# Sheet1.net
KiCad netlist of a schematic drawn in Altium Designer
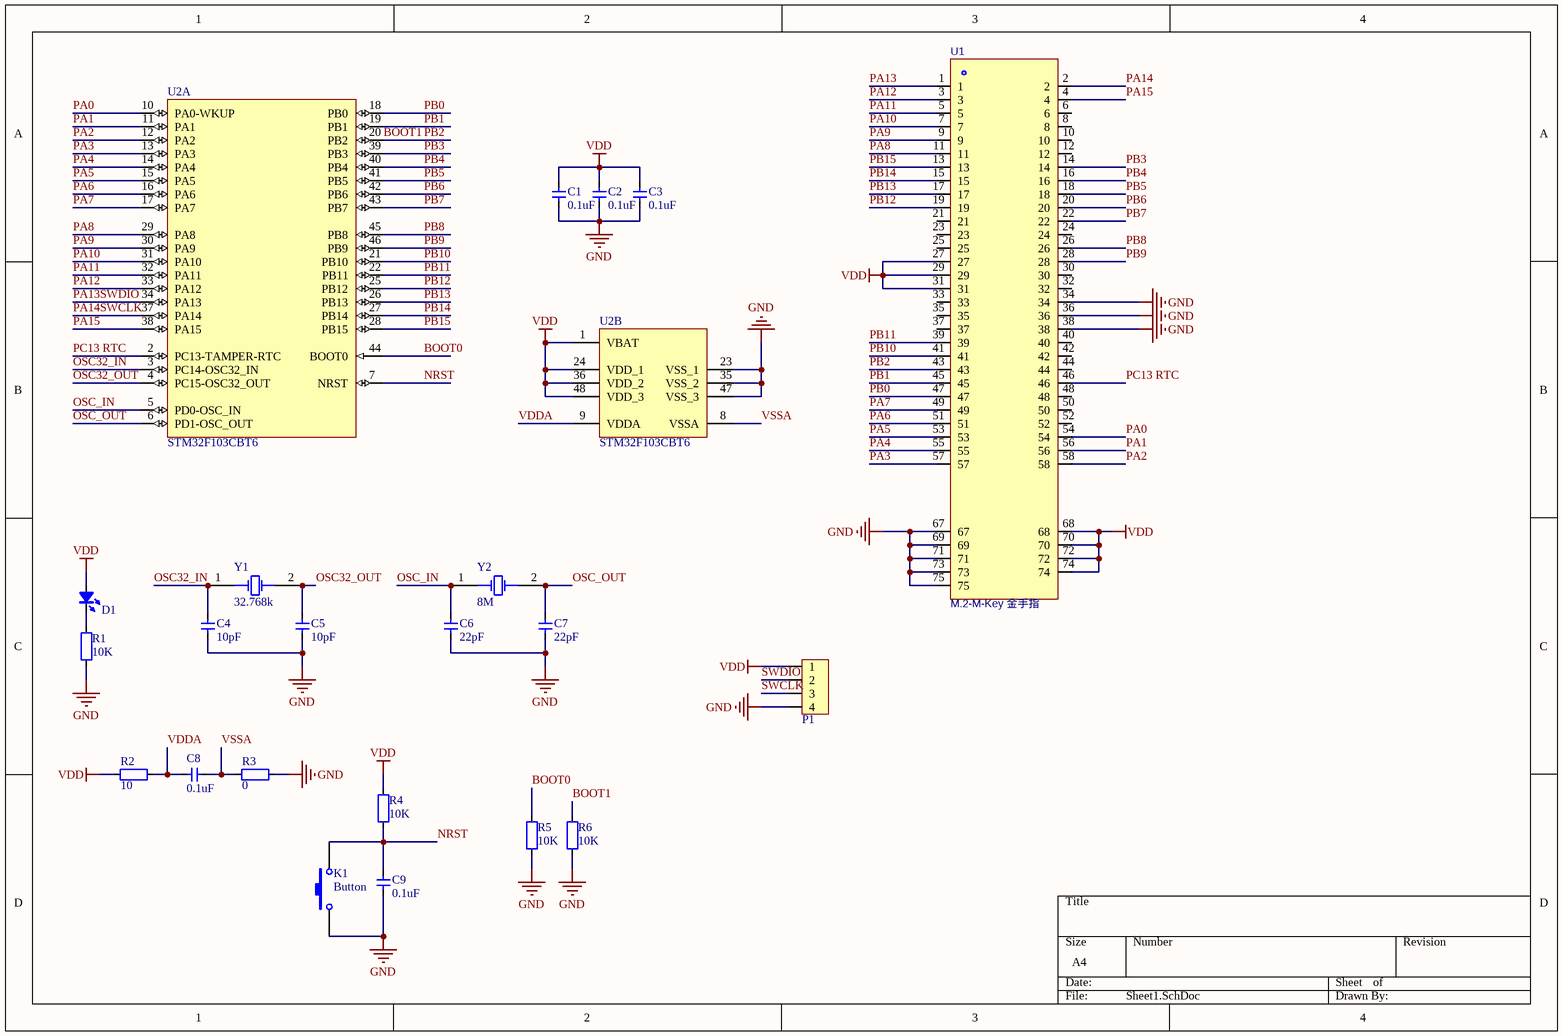
[diagram p0: Sheet1.SchDoc]

(export (version "E")
  (design (tool "Eeschema 10.0.6"))
  (components
    (comp (ref "C1")
      (value "0.1uF")
      (footprint "C0603")
      (description "Capacitor")
      (fields (field (name "PUBLISHER") "Altium Limited"))
      (libsource (lib "lycraft_lib") (part "贴片C"))
    )
    (comp (ref "C2")
      (value "0.1uF")
      (footprint "C0603")
      (description "Capacitor")
      (fields (field (name "PUBLISHER") "Altium Limited"))
      (libsource (lib "lycraft_lib") (part "贴片C"))
    )
    (comp (ref "C3")
      (value "0.1uF")
      (footprint "C0603")
      (description "Capacitor")
      (fields (field (name "PUBLISHER") "Altium Limited"))
      (libsource (lib "lycraft_lib") (part "贴片C"))
    )
    (comp (ref "C4")
      (value "10pF")
      (footprint "C0603")
      (description "Capacitor")
      (fields (field (name "PUBLISHER") "Altium Limited"))
      (libsource (lib "lycraft_lib") (part "贴片C"))
    )
    (comp (ref "C5")
      (value "10pF")
      (footprint "C0603")
      (description "Capacitor")
      (fields (field (name "PUBLISHER") "Altium Limited"))
      (libsource (lib "lycraft_lib") (part "贴片C"))
    )
    (comp (ref "C6")
      (value "22pF")
      (footprint "C0603")
      (description "Capacitor")
      (fields (field (name "PUBLISHER") "Altium Limited"))
      (libsource (lib "lycraft_lib") (part "贴片C"))
    )
    (comp (ref "C7")
      (value "22pF")
      (footprint "C0603")
      (description "Capacitor")
      (fields (field (name "PUBLISHER") "Altium Limited"))
      (libsource (lib "lycraft_lib") (part "贴片C"))
    )
    (comp (ref "C8")
      (value "0.1uF")
      (footprint "C0603")
      (description "Capacitor")
      (fields (field (name "PUBLISHER") "Altium Limited"))
      (libsource (lib "lycraft_lib") (part "贴片C"))
    )
    (comp (ref "C9")
      (value "0.1uF")
      (footprint "C0603")
      (description "Capacitor")
      (fields (field (name "PUBLISHER") "Altium Limited"))
      (libsource (lib "lycraft_lib") (part "贴片C"))
    )
    (comp (ref "D1")
      (value "color?")
      (footprint "LED0603")
      (description "LED")
      (libsource (lib "lycraft_lib") (part "贴片LED"))
    )
    (comp (ref "K1")
      (value "Button")
      (footprint "BUTTON-K2")
      (fields (field (name "PUBLISHER") "Altium Limited"))
      (libsource (lib "lycraft_lib") (part "Button"))
    )
    (comp (ref "P1")
      (value "HDR1x4_2.0")
      (footprint "HDR 4_2")
      (libsource (lib "Pzh_Lib") (part "HDR1x4_2.0"))
    )
    (comp (ref "R1")
      (value "10K")
      (footprint "R0603")
      (description "Resistor")
      (fields (field (name "PUBLISHER") "Altium Limited"))
      (libsource (lib "lycraft_lib") (part "贴片R"))
    )
    (comp (ref "R2")
      (value "10")
      (footprint "R0603")
      (description "Resistor")
      (fields (field (name "PUBLISHER") "Altium Limited"))
      (libsource (lib "") (part "贴片R_1"))
    )
    (comp (ref "R3")
      (value "0")
      (footprint "R0603")
      (description "Resistor")
      (fields (field (name "PUBLISHER") "Altium Limited"))
      (libsource (lib "") (part "贴片R_1"))
    )
    (comp (ref "R4")
      (value "10K")
      (footprint "R0603")
      (description "Resistor")
      (fields (field (name "PUBLISHER") "Altium Limited"))
      (libsource (lib "lycraft_lib") (part "贴片R"))
    )
    (comp (ref "R5")
      (value "10K")
      (footprint "R0603")
      (description "Resistor")
      (fields (field (name "PUBLISHER") "Altium Limited"))
      (libsource (lib "lycraft_lib") (part "贴片R"))
    )
    (comp (ref "R6")
      (value "10K")
      (footprint "R0603")
      (description "Resistor")
      (fields (field (name "PUBLISHER") "Altium Limited"))
      (libsource (lib "lycraft_lib") (part "贴片R"))
    )
    (comp (ref "U1")
      (value "M.2-M-Key 金手指")
      (footprint "M.2_NGFF")
      (fields (field (name "CONTRIBUTOR") "zengjf"))
      (libsource (lib "接插件") (part "M.2-M-Key 金手指"))
    )
    (comp (ref "U2")
      (value "STM32F103CBT6")
      (footprint "STM-LQFP48_N")
      (libsource (lib "MCU") (part "STM32F103CBT6"))
    )
    (comp (ref "Y1")
      (value "XTAL 32.768KHz 2P")
      (footprint "3215 2Pin")
      (fields (field (name "ALTIUM_UNNAMED_1") "32.768k"))
      (libsource (lib "lycraft_lib") (part "XTAL 32.768KHz 2P"))
    )
    (comp (ref "Y2")
      (value "8M")
      (footprint "5032 2Pin")
      (libsource (lib "lycraft_lib") (part "XTAL 8Mhz 2pin"))
    )
  )
  (nets
    (net (code "1") (name "/BOOT0") (class "Default")
      (node (ref "R5") (pin "2") (pinfunction "2_2") (pintype "passive"))
      (node (ref "U2") (pin "44") (pinfunction "BOOT0_44") (pintype "input"))
    )
    (net (code "2") (name "/BOOT1") (class "Default")
      (node (ref "R6") (pin "2") (pinfunction "2_2") (pintype "passive"))
      (node (ref "U1") (pin "43") (pinfunction "43_43") (pintype "passive"))
      (node (ref "U2") (pin "20") (pinfunction "PB2_20") (pintype "bidirectional"))
    )
    (net (code "3") (name "/NRST") (class "Default")
      (node (ref "C9") (pin "2") (pinfunction "2_2") (pintype "passive"))
      (node (ref "K1") (pin "2") (pinfunction "2_2") (pintype "passive"))
      (node (ref "R4") (pin "1") (pinfunction "1_1") (pintype "passive"))
      (node (ref "U2") (pin "7") (pinfunction "NRST_7") (pintype "bidirectional"))
    )
    (net (code "4") (name "/OSC32_IN") (class "Default")
      (node (ref "C4") (pin "2") (pinfunction "2_2") (pintype "passive"))
      (node (ref "U2") (pin "3") (pinfunction "PC14-OSC32_IN_3") (pintype "bidirectional"))
      (node (ref "Y1") (pin "1") (pinfunction "OSC1_1") (pintype "passive"))
    )
    (net (code "5") (name "/OSC32_OUT") (class "Default")
      (node (ref "C5") (pin "2") (pinfunction "2_2") (pintype "passive"))
      (node (ref "U2") (pin "4") (pinfunction "PC15-OSC32_OUT_4") (pintype "bidirectional"))
      (node (ref "Y1") (pin "2") (pinfunction "OSC2_2") (pintype "passive"))
    )
    (net (code "6") (name "/OSC_IN") (class "Default")
      (node (ref "C6") (pin "2") (pinfunction "2_2") (pintype "passive"))
      (node (ref "U2") (pin "5") (pinfunction "PD0-OSC_IN_5") (pintype "bidirectional"))
      (node (ref "Y2") (pin "1") (pinfunction "OSC1_1") (pintype "passive"))
    )
    (net (code "7") (name "/OSC_OUT") (class "Default")
      (node (ref "C7") (pin "2") (pinfunction "2_2") (pintype "passive"))
      (node (ref "U2") (pin "6") (pinfunction "PD1-OSC_OUT_6") (pintype "bidirectional"))
      (node (ref "Y2") (pin "2") (pinfunction "OSC2_2") (pintype "passive"))
    )
    (net (code "8") (name "/PA0") (class "Default")
      (node (ref "U1") (pin "54") (pinfunction "54_54") (pintype "passive"))
      (node (ref "U2") (pin "10") (pinfunction "PA0-WKUP_10") (pintype "bidirectional"))
    )
    (net (code "9") (name "/PA1") (class "Default")
      (node (ref "U1") (pin "56") (pinfunction "56_56") (pintype "passive"))
      (node (ref "U2") (pin "11") (pinfunction "PA1_11") (pintype "bidirectional"))
    )
    (net (code "10") (name "/PA2") (class "Default")
      (node (ref "U1") (pin "58") (pinfunction "58_58") (pintype "passive"))
      (node (ref "U2") (pin "12") (pinfunction "PA2_12") (pintype "bidirectional"))
    )
    (net (code "11") (name "/PA3") (class "Default")
      (node (ref "U1") (pin "57") (pinfunction "57_57") (pintype "passive"))
      (node (ref "U2") (pin "13") (pinfunction "PA3_13") (pintype "bidirectional"))
    )
    (net (code "12") (name "/PA4") (class "Default")
      (node (ref "U1") (pin "55") (pinfunction "55_55") (pintype "passive"))
      (node (ref "U2") (pin "14") (pinfunction "PA4_14") (pintype "bidirectional"))
    )
    (net (code "13") (name "/PA5") (class "Default")
      (node (ref "U1") (pin "53") (pinfunction "53_53") (pintype "passive"))
      (node (ref "U2") (pin "15") (pinfunction "PA5_15") (pintype "bidirectional"))
    )
    (net (code "14") (name "/PA6") (class "Default")
      (node (ref "U1") (pin "51") (pinfunction "51_51") (pintype "passive"))
      (node (ref "U2") (pin "16") (pinfunction "PA6_16") (pintype "bidirectional"))
    )
    (net (code "15") (name "/PA7") (class "Default")
      (node (ref "U1") (pin "49") (pinfunction "49_49") (pintype "passive"))
      (node (ref "U2") (pin "17") (pinfunction "PA7_17") (pintype "bidirectional"))
    )
    (net (code "16") (name "/PA8") (class "Default")
      (node (ref "U1") (pin "11") (pinfunction "11_11") (pintype "passive"))
      (node (ref "U2") (pin "29") (pinfunction "PA8_29") (pintype "bidirectional"))
    )
    (net (code "17") (name "/PA9") (class "Default")
      (node (ref "U1") (pin "9") (pinfunction "9_9") (pintype "passive"))
      (node (ref "U2") (pin "30") (pinfunction "PA9_30") (pintype "bidirectional"))
    )
    (net (code "18") (name "/PA10") (class "Default")
      (node (ref "U1") (pin "7") (pinfunction "7_7") (pintype "passive"))
      (node (ref "U2") (pin "31") (pinfunction "PA10_31") (pintype "bidirectional"))
    )
    (net (code "19") (name "/PA11") (class "Default")
      (node (ref "U1") (pin "5") (pinfunction "5_5") (pintype "passive"))
      (node (ref "U2") (pin "32") (pinfunction "PA11_32") (pintype "bidirectional"))
    )
    (net (code "20") (name "/PA12") (class "Default")
      (node (ref "U1") (pin "3") (pinfunction "3_3") (pintype "passive"))
      (node (ref "U2") (pin "33") (pinfunction "PA12_33") (pintype "bidirectional"))
    )
    (net (code "21") (name "/PA13") (class "Default")
      (node (ref "P1") (pin "2") (pinfunction "2_2") (pintype "passive"))
      (node (ref "U1") (pin "1") (pinfunction "1_1") (pintype "passive"))
      (node (ref "U2") (pin "34") (pinfunction "PA13_34") (pintype "bidirectional"))
    )
    (net (code "22") (name "/PA14") (class "Default")
      (node (ref "P1") (pin "3") (pinfunction "3_3") (pintype "passive"))
      (node (ref "U1") (pin "2") (pinfunction "2_2") (pintype "passive"))
      (node (ref "U2") (pin "37") (pinfunction "PA14_37") (pintype "bidirectional"))
    )
    (net (code "23") (name "/PA15") (class "Default")
      (node (ref "U1") (pin "4") (pinfunction "4_4") (pintype "passive"))
      (node (ref "U2") (pin "38") (pinfunction "PA15_38") (pintype "bidirectional"))
    )
    (net (code "24") (name "/PB0") (class "Default")
      (node (ref "U1") (pin "47") (pinfunction "47_47") (pintype "passive"))
      (node (ref "U2") (pin "18") (pinfunction "PB0_18") (pintype "bidirectional"))
    )
    (net (code "25") (name "/PB1") (class "Default")
      (node (ref "U1") (pin "45") (pinfunction "45_45") (pintype "passive"))
      (node (ref "U2") (pin "19") (pinfunction "PB1_19") (pintype "bidirectional"))
    )
    (net (code "26") (name "/PB3") (class "Default")
      (node (ref "U1") (pin "14") (pinfunction "14_14") (pintype "passive"))
      (node (ref "U2") (pin "39") (pinfunction "PB3_39") (pintype "bidirectional"))
    )
    (net (code "27") (name "/PB4") (class "Default")
      (node (ref "U1") (pin "16") (pinfunction "16_16") (pintype "passive"))
      (node (ref "U2") (pin "40") (pinfunction "PB4_40") (pintype "bidirectional"))
    )
    (net (code "28") (name "/PB5") (class "Default")
      (node (ref "U1") (pin "18") (pinfunction "18_18") (pintype "passive"))
      (node (ref "U2") (pin "41") (pinfunction "PB5_41") (pintype "bidirectional"))
    )
    (net (code "29") (name "/PB6") (class "Default")
      (node (ref "U1") (pin "20") (pinfunction "20_20") (pintype "passive"))
      (node (ref "U2") (pin "42") (pinfunction "PB6_42") (pintype "bidirectional"))
    )
    (net (code "30") (name "/PB7") (class "Default")
      (node (ref "U1") (pin "22") (pinfunction "22_22") (pintype "passive"))
      (node (ref "U2") (pin "43") (pinfunction "PB7_43") (pintype "bidirectional"))
    )
    (net (code "31") (name "/PB8") (class "Default")
      (node (ref "U1") (pin "26") (pinfunction "26_26") (pintype "passive"))
      (node (ref "U2") (pin "45") (pinfunction "PB8_45") (pintype "bidirectional"))
    )
    (net (code "32") (name "/PB9") (class "Default")
      (node (ref "U1") (pin "28") (pinfunction "28_28") (pintype "passive"))
      (node (ref "U2") (pin "46") (pinfunction "PB9_46") (pintype "bidirectional"))
    )
    (net (code "33") (name "/PB10") (class "Default")
      (node (ref "U1") (pin "41") (pinfunction "41_41") (pintype "passive"))
      (node (ref "U2") (pin "21") (pinfunction "PB10_21") (pintype "bidirectional"))
    )
    (net (code "34") (name "/PB11") (class "Default")
      (node (ref "U1") (pin "39") (pinfunction "39_39") (pintype "passive"))
      (node (ref "U2") (pin "22") (pinfunction "PB11_22") (pintype "bidirectional"))
    )
    (net (code "35") (name "/PB12") (class "Default")
      (node (ref "U1") (pin "19") (pinfunction "19_19") (pintype "passive"))
      (node (ref "U2") (pin "25") (pinfunction "PB12_25") (pintype "bidirectional"))
    )
    (net (code "36") (name "/PB13") (class "Default")
      (node (ref "U1") (pin "17") (pinfunction "17_17") (pintype "passive"))
      (node (ref "U2") (pin "26") (pinfunction "PB13_26") (pintype "bidirectional"))
    )
    (net (code "37") (name "/PB14") (class "Default")
      (node (ref "U1") (pin "15") (pinfunction "15_15") (pintype "passive"))
      (node (ref "U2") (pin "27") (pinfunction "PB14_27") (pintype "bidirectional"))
    )
    (net (code "38") (name "/PB15") (class "Default")
      (node (ref "U1") (pin "13") (pinfunction "13_13") (pintype "passive"))
      (node (ref "U2") (pin "28") (pinfunction "PB15_28") (pintype "bidirectional"))
    )
    (net (code "39") (name "/PC13 RTC") (class "Default")
      (node (ref "U1") (pin "46") (pinfunction "46_46") (pintype "passive"))
      (node (ref "U2") (pin "2") (pinfunction "PC13-TAMPER-RTC_2") (pintype "bidirectional"))
    )
    (net (code "40") (name "/VDDA") (class "Default")
      (node (ref "C8") (pin "1") (pinfunction "1_1") (pintype "passive"))
      (node (ref "R2") (pin "2") (pinfunction "2_2") (pintype "passive"))
      (node (ref "U2") (pin "9") (pinfunction "VDDA_9") (pintype "power_in"))
    )
    (net (code "41") (name "/VSSA") (class "Default")
      (node (ref "C8") (pin "2") (pinfunction "2_2") (pintype "passive"))
      (node (ref "R3") (pin "1") (pinfunction "1_1") (pintype "passive"))
      (node (ref "U2") (pin "8") (pinfunction "VSSA_8") (pintype "power_in"))
    )
    (net (code "42") (name "GND") (class "Default")
      (node (ref "C1") (pin "1") (pinfunction "1_1") (pintype "passive"))
      (node (ref "C2") (pin "1") (pinfunction "1_1") (pintype "passive"))
      (node (ref "C3") (pin "1") (pinfunction "1_1") (pintype "passive"))
      (node (ref "C4") (pin "1") (pinfunction "1_1") (pintype "passive"))
      (node (ref "C5") (pin "1") (pinfunction "1_1") (pintype "passive"))
      (node (ref "C6") (pin "1") (pinfunction "1_1") (pintype "passive"))
      (node (ref "C7") (pin "1") (pinfunction "1_1") (pintype "passive"))
      (node (ref "C9") (pin "1") (pinfunction "1_1") (pintype "passive"))
      (node (ref "K1") (pin "1") (pinfunction "1_1") (pintype "passive"))
      (node (ref "P1") (pin "4") (pinfunction "4_4") (pintype "passive"))
      (node (ref "R1") (pin "1") (pinfunction "1_1") (pintype "passive"))
      (node (ref "R3") (pin "2") (pinfunction "2_2") (pintype "passive"))
      (node (ref "R5") (pin "1") (pinfunction "1_1") (pintype "passive"))
      (node (ref "R6") (pin "1") (pinfunction "1_1") (pintype "passive"))
      (node (ref "U1") (pin "34") (pinfunction "34_34") (pintype "passive"))
      (node (ref "U1") (pin "36") (pinfunction "36_36") (pintype "passive"))
      (node (ref "U1") (pin "38") (pinfunction "38_38") (pintype "passive"))
      (node (ref "U1") (pin "67") (pinfunction "67_67") (pintype "passive"))
      (node (ref "U1") (pin "69") (pinfunction "69_69") (pintype "passive"))
      (node (ref "U1") (pin "71") (pinfunction "71_71") (pintype "passive"))
      (node (ref "U1") (pin "73") (pinfunction "73_73") (pintype "passive"))
      (node (ref "U1") (pin "75") (pinfunction "75_75") (pintype "passive"))
      (node (ref "U2") (pin "23") (pinfunction "VSS_1_23") (pintype "power_in"))
      (node (ref "U2") (pin "35") (pinfunction "VSS_2_35") (pintype "power_in"))
      (node (ref "U2") (pin "47") (pinfunction "VSS_3_47") (pintype "power_in"))
    )
    (net (code "43") (name "Net-(D1-K)") (class "Default")
      (node (ref "D1") (pin "2") (pinfunction "K_2") (pintype "passive"))
      (node (ref "R1") (pin "2") (pinfunction "2_2") (pintype "passive"))
    )
    (net (code "44") (name "VDD") (class "Default")
      (node (ref "C1") (pin "2") (pinfunction "2_2") (pintype "passive"))
      (node (ref "C2") (pin "2") (pinfunction "2_2") (pintype "passive"))
      (node (ref "C3") (pin "2") (pinfunction "2_2") (pintype "passive"))
      (node (ref "D1") (pin "1") (pinfunction "A_1") (pintype "passive"))
      (node (ref "P1") (pin "1") (pinfunction "1_1") (pintype "passive"))
      (node (ref "R2") (pin "1") (pinfunction "1_1") (pintype "passive"))
      (node (ref "R4") (pin "2") (pinfunction "2_2") (pintype "passive"))
      (node (ref "U1") (pin "27") (pinfunction "27_27") (pintype "passive"))
      (node (ref "U1") (pin "29") (pinfunction "29_29") (pintype "passive"))
      (node (ref "U1") (pin "31") (pinfunction "31_31") (pintype "passive"))
      (node (ref "U1") (pin "68") (pinfunction "68_68") (pintype "passive"))
      (node (ref "U1") (pin "70") (pinfunction "70_70") (pintype "passive"))
      (node (ref "U1") (pin "72") (pinfunction "72_72") (pintype "passive"))
      (node (ref "U1") (pin "74") (pinfunction "74_74") (pintype "passive"))
      (node (ref "U2") (pin "1") (pinfunction "VBAT_1") (pintype "power_in"))
      (node (ref "U2") (pin "24") (pinfunction "VDD_1_24") (pintype "power_in"))
      (node (ref "U2") (pin "36") (pinfunction "VDD_2_36") (pintype "power_in"))
      (node (ref "U2") (pin "48") (pinfunction "VDD_3_48") (pintype "power_in"))
    )
    (net (code "45") (name "unconnected-(U1-Pad6)") (class "Default")
      (node (ref "U1") (pin "6") (pinfunction "6_6") (pintype "passive"))
    )
    (net (code "46") (name "unconnected-(U1-Pad8)") (class "Default")
      (node (ref "U1") (pin "8") (pinfunction "8_8") (pintype "passive"))
    )
    (net (code "47") (name "unconnected-(U1-Pad10)") (class "Default")
      (node (ref "U1") (pin "10") (pinfunction "10_10") (pintype "passive"))
    )
    (net (code "48") (name "unconnected-(U1-Pad12)") (class "Default")
      (node (ref "U1") (pin "12") (pinfunction "12_12") (pintype "passive"))
    )
    (net (code "49") (name "unconnected-(U1-Pad21)") (class "Default")
      (node (ref "U1") (pin "21") (pinfunction "21_21") (pintype "passive"))
    )
    (net (code "50") (name "unconnected-(U1-Pad23)") (class "Default")
      (node (ref "U1") (pin "23") (pinfunction "23_23") (pintype "passive"))
    )
    (net (code "51") (name "unconnected-(U1-Pad24)") (class "Default")
      (node (ref "U1") (pin "24") (pinfunction "24_24") (pintype "passive"))
    )
    (net (code "52") (name "unconnected-(U1-Pad25)") (class "Default")
      (node (ref "U1") (pin "25") (pinfunction "25_25") (pintype "passive"))
    )
    (net (code "53") (name "unconnected-(U1-Pad30)") (class "Default")
      (node (ref "U1") (pin "30") (pinfunction "30_30") (pintype "passive"))
    )
    (net (code "54") (name "unconnected-(U1-Pad32)") (class "Default")
      (node (ref "U1") (pin "32") (pinfunction "32_32") (pintype "passive"))
    )
    (net (code "55") (name "unconnected-(U1-Pad33)") (class "Default")
      (node (ref "U1") (pin "33") (pinfunction "33_33") (pintype "passive"))
    )
    (net (code "56") (name "unconnected-(U1-Pad35)") (class "Default")
      (node (ref "U1") (pin "35") (pinfunction "35_35") (pintype "passive"))
    )
    (net (code "57") (name "unconnected-(U1-Pad37)") (class "Default")
      (node (ref "U1") (pin "37") (pinfunction "37_37") (pintype "passive"))
    )
    (net (code "58") (name "unconnected-(U1-Pad40)") (class "Default")
      (node (ref "U1") (pin "40") (pinfunction "40_40") (pintype "passive"))
    )
    (net (code "59") (name "unconnected-(U1-Pad42)") (class "Default")
      (node (ref "U1") (pin "42") (pinfunction "42_42") (pintype "passive"))
    )
    (net (code "60") (name "unconnected-(U1-Pad44)") (class "Default")
      (node (ref "U1") (pin "44") (pinfunction "44_44") (pintype "passive"))
    )
    (net (code "61") (name "unconnected-(U1-Pad48)") (class "Default")
      (node (ref "U1") (pin "48") (pinfunction "48_48") (pintype "passive"))
    )
    (net (code "62") (name "unconnected-(U1-Pad50)") (class "Default")
      (node (ref "U1") (pin "50") (pinfunction "50_50") (pintype "passive"))
    )
    (net (code "63") (name "unconnected-(U1-Pad52)") (class "Default")
      (node (ref "U1") (pin "52") (pinfunction "52_52") (pintype "passive"))
    )
  )
)
